# Connector_Sheet.net
KiCad netlist of a schematic drawn in Altium Designer
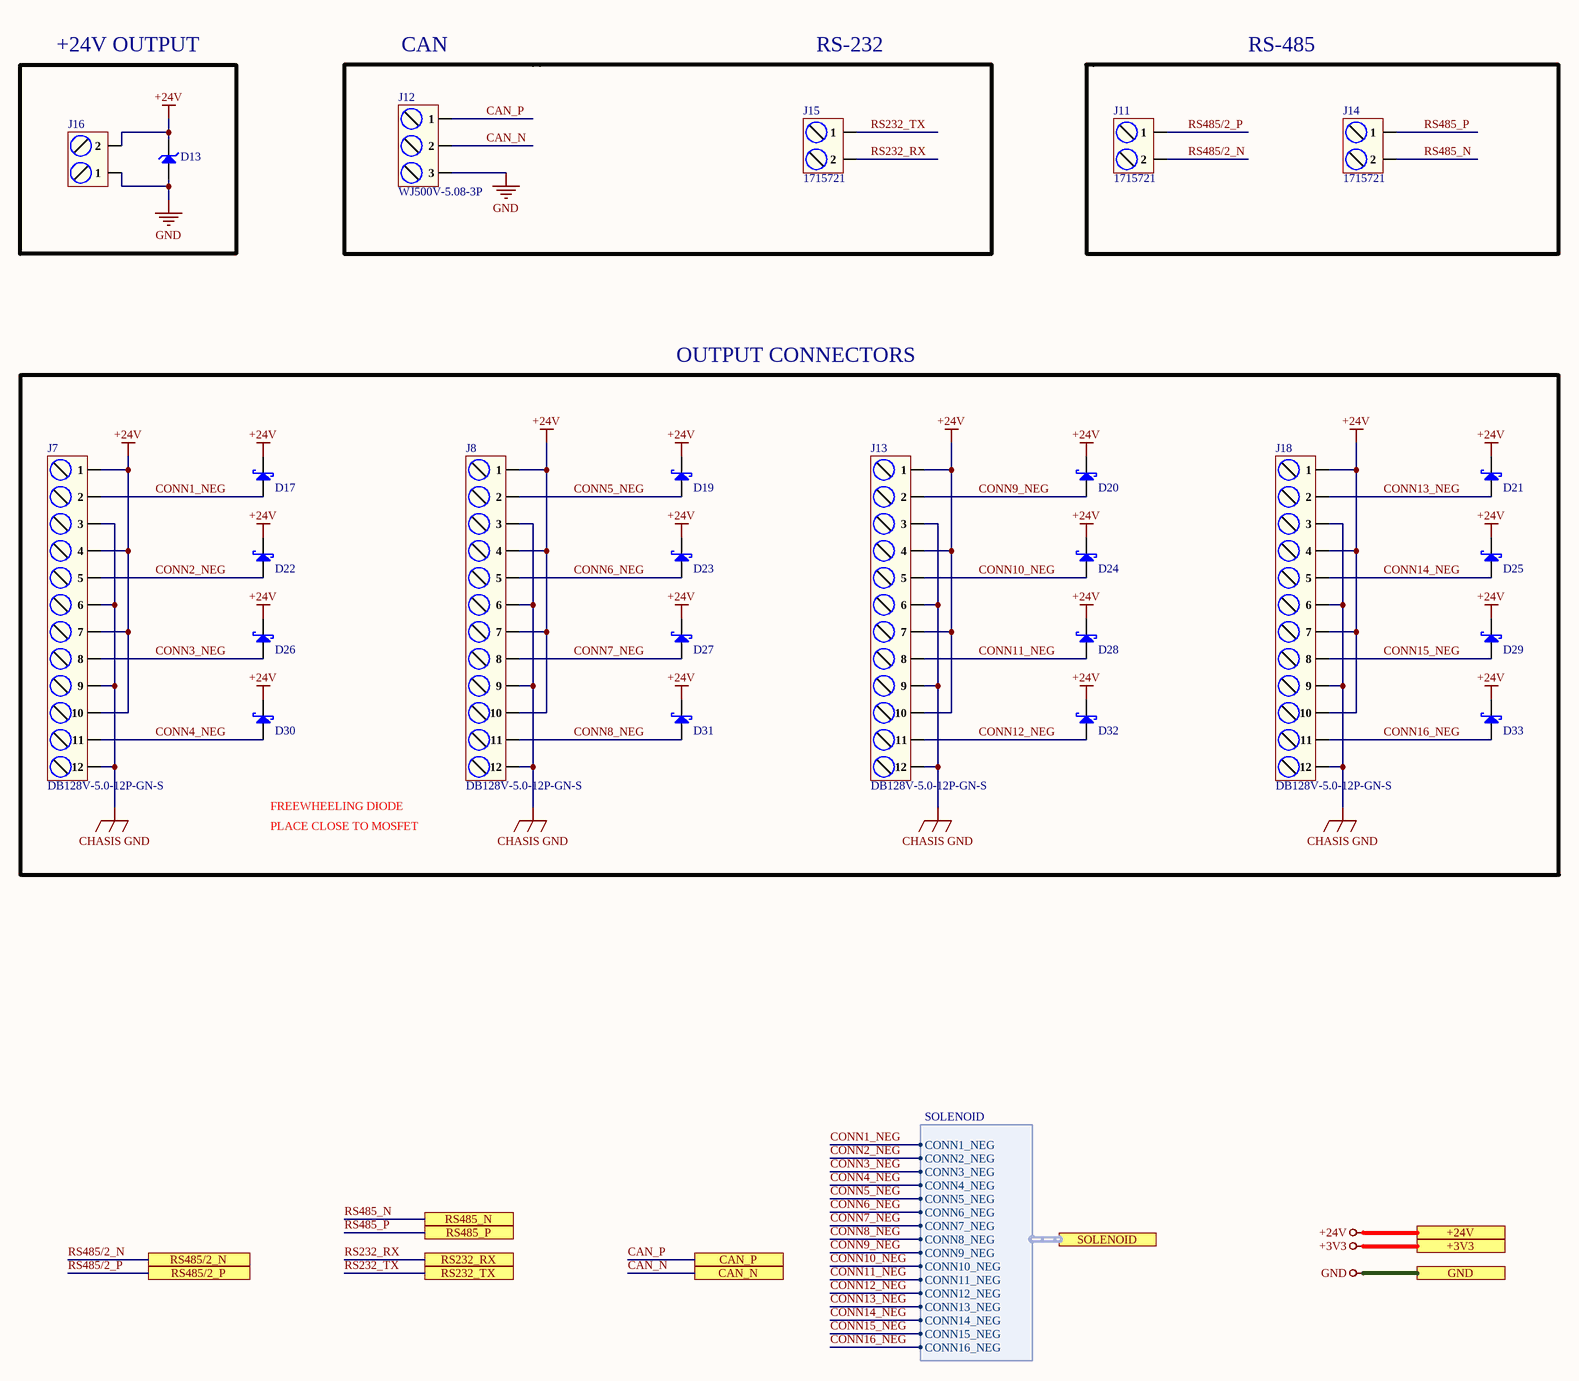
[diagram p0: Connector_Sheet.SchDoc]

(export (version "E")
  (design (tool "Eeschema 10.0.6"))
  (components
    (comp (ref "D13")
      (value "SMBJ28A-13-F")
      (footprint "SMB_")
      (description "TVS DIODE 28VWM 45.4VC SMB")
      (fields (field (name "MANUFACTURER") "Diodes"))
      (libsource (lib "eSpark Libraries") (part "SMBJ28A-13-F"))
    )
    (comp (ref "D17")
      (value "B150-13-F")
      (footprint "SMA")
      (description "DIODE SCHOTTKY 50V 1A SMA")
      (fields (field (name "MANUFACTURER") "Diodes Incorporated") (field (name "LCSC PART NUMBER") "C134431"))
      (libsource (lib "eSpark Libraries") (part "B150-13-F"))
    )
    (comp (ref "D19")
      (value "B150-13-F")
      (footprint "SMA")
      (description "DIODE SCHOTTKY 50V 1A SMA")
      (fields (field (name "MANUFACTURER") "Diodes Incorporated") (field (name "LCSC PART NUMBER") "C134431"))
      (libsource (lib "eSpark Libraries") (part "B150-13-F"))
    )
    (comp (ref "D20")
      (value "B150-13-F")
      (footprint "SMA")
      (description "DIODE SCHOTTKY 50V 1A SMA")
      (fields (field (name "MANUFACTURER") "Diodes Incorporated") (field (name "LCSC PART NUMBER") "C134431"))
      (libsource (lib "eSpark Libraries") (part "B150-13-F"))
    )
    (comp (ref "D21")
      (value "B150-13-F")
      (footprint "SMA")
      (description "DIODE SCHOTTKY 50V 1A SMA")
      (fields (field (name "MANUFACTURER") "Diodes Incorporated") (field (name "LCSC PART NUMBER") "C134431"))
      (libsource (lib "eSpark Libraries") (part "B150-13-F"))
    )
    (comp (ref "D22")
      (value "B150-13-F")
      (footprint "SMA")
      (description "DIODE SCHOTTKY 50V 1A SMA")
      (fields (field (name "MANUFACTURER") "Diodes Incorporated") (field (name "LCSC PART NUMBER") "C134431"))
      (libsource (lib "eSpark Libraries") (part "B150-13-F"))
    )
    (comp (ref "D23")
      (value "B150-13-F")
      (footprint "SMA")
      (description "DIODE SCHOTTKY 50V 1A SMA")
      (fields (field (name "MANUFACTURER") "Diodes Incorporated") (field (name "LCSC PART NUMBER") "C134431"))
      (libsource (lib "eSpark Libraries") (part "B150-13-F"))
    )
    (comp (ref "D24")
      (value "B150-13-F")
      (footprint "SMA")
      (description "DIODE SCHOTTKY 50V 1A SMA")
      (fields (field (name "MANUFACTURER") "Diodes Incorporated") (field (name "LCSC PART NUMBER") "C134431"))
      (libsource (lib "eSpark Libraries") (part "B150-13-F"))
    )
    (comp (ref "D25")
      (value "B150-13-F")
      (footprint "SMA")
      (description "DIODE SCHOTTKY 50V 1A SMA")
      (fields (field (name "MANUFACTURER") "Diodes Incorporated") (field (name "LCSC PART NUMBER") "C134431"))
      (libsource (lib "eSpark Libraries") (part "B150-13-F"))
    )
    (comp (ref "D26")
      (value "B150-13-F")
      (footprint "SMA")
      (description "DIODE SCHOTTKY 50V 1A SMA")
      (fields (field (name "MANUFACTURER") "Diodes Incorporated") (field (name "LCSC PART NUMBER") "C134431"))
      (libsource (lib "eSpark Libraries") (part "B150-13-F"))
    )
    (comp (ref "D27")
      (value "B150-13-F")
      (footprint "SMA")
      (description "DIODE SCHOTTKY 50V 1A SMA")
      (fields (field (name "MANUFACTURER") "Diodes Incorporated") (field (name "LCSC PART NUMBER") "C134431"))
      (libsource (lib "eSpark Libraries") (part "B150-13-F"))
    )
    (comp (ref "D28")
      (value "B150-13-F")
      (footprint "SMA")
      (description "DIODE SCHOTTKY 50V 1A SMA")
      (fields (field (name "MANUFACTURER") "Diodes Incorporated") (field (name "LCSC PART NUMBER") "C134431"))
      (libsource (lib "eSpark Libraries") (part "B150-13-F"))
    )
    (comp (ref "D29")
      (value "B150-13-F")
      (footprint "SMA")
      (description "DIODE SCHOTTKY 50V 1A SMA")
      (fields (field (name "MANUFACTURER") "Diodes Incorporated") (field (name "LCSC PART NUMBER") "C134431"))
      (libsource (lib "eSpark Libraries") (part "B150-13-F"))
    )
    (comp (ref "D30")
      (value "B150-13-F")
      (footprint "SMA")
      (description "DIODE SCHOTTKY 50V 1A SMA")
      (fields (field (name "MANUFACTURER") "Diodes Incorporated") (field (name "LCSC PART NUMBER") "C134431"))
      (libsource (lib "eSpark Libraries") (part "B150-13-F"))
    )
    (comp (ref "D31")
      (value "B150-13-F")
      (footprint "SMA")
      (description "DIODE SCHOTTKY 50V 1A SMA")
      (fields (field (name "MANUFACTURER") "Diodes Incorporated") (field (name "LCSC PART NUMBER") "C134431"))
      (libsource (lib "eSpark Libraries") (part "B150-13-F"))
    )
    (comp (ref "D32")
      (value "B150-13-F")
      (footprint "SMA")
      (description "DIODE SCHOTTKY 50V 1A SMA")
      (fields (field (name "MANUFACTURER") "Diodes Incorporated") (field (name "LCSC PART NUMBER") "C134431"))
      (libsource (lib "eSpark Libraries") (part "B150-13-F"))
    )
    (comp (ref "D33")
      (value "B150-13-F")
      (footprint "SMA")
      (description "DIODE SCHOTTKY 50V 1A SMA")
      (fields (field (name "MANUFACTURER") "Diodes Incorporated") (field (name "LCSC PART NUMBER") "C134431"))
      (libsource (lib "eSpark Libraries") (part "B150-13-F"))
    )
    (comp (ref "J7")
      (value "DB128V-5.0-12P-GN-S")
      (footprint "DB128V-5.0-12P-GN-S")
      (fields (field (name "MANUFACTURER") "DORABO") (field (name "LCSC PART NUMBER") "C424688"))
      (libsource (lib "eSpark Libraries") (part "DB128V-5.0-12P-GN-S"))
    )
    (comp (ref "J8")
      (value "DB128V-5.0-12P-GN-S")
      (footprint "DB128V-5.0-12P-GN-S")
      (fields (field (name "MANUFACTURER") "DORABO") (field (name "LCSC PART NUMBER") "C424688"))
      (libsource (lib "eSpark Libraries") (part "DB128V-5.0-12P-GN-S"))
    )
    (comp (ref "J11")
      (value "1715721")
      (footprint "1715721")
      (description "TERM BLK 2P SIDE ENT 5.08MM PCB")
      (fields (field (name "MANUFACTURER") "Phoenix Contact"))
      (libsource (lib "eSpark Libraries") (part "1715721"))
    )
    (comp (ref "J12")
      (value "WJ500V-5.08-3P")
      (footprint "WJ500V-5.08-3P")
      (fields (field (name "MANUFACTURER") "Ningbo Kangnex Elec") (field (name "LCSC PART NUMBER") "C72334"))
      (libsource (lib "eSpark Libraries") (part "WJ500V-5.08-3P"))
    )
    (comp (ref "J13")
      (value "DB128V-5.0-12P-GN-S")
      (footprint "DB128V-5.0-12P-GN-S")
      (fields (field (name "MANUFACTURER") "DORABO") (field (name "LCSC PART NUMBER") "C424688"))
      (libsource (lib "eSpark Libraries") (part "DB128V-5.0-12P-GN-S"))
    )
    (comp (ref "J14")
      (value "1715721")
      (footprint "1715721")
      (description "TERM BLK 2P SIDE ENT 5.08MM PCB")
      (fields (field (name "MANUFACTURER") "Phoenix Contact"))
      (libsource (lib "eSpark Libraries") (part "1715721"))
    )
    (comp (ref "J15")
      (value "1715721")
      (footprint "1715721")
      (description "TERM BLK 2P SIDE ENT 5.08MM PCB")
      (fields (field (name "MANUFACTURER") "Phoenix Contact"))
      (libsource (lib "eSpark Libraries") (part "1715721"))
    )
    (comp (ref "J16")
      (value "MXHB9500-9.5-02P-BK01-Cu-S-A")
      (footprint "MXHB9500-9.5-02P-BK01-Cu-S-A")
      (fields (field (name "MANUFACTURER") "MAX") (field (name "LCSC PART NUMBER") "C7542168"))
      (libsource (lib "eSpark Libraries") (part "MXHB9500-9.5-02P-BK01-Cu-S-A"))
    )
    (comp (ref "J18")
      (value "DB128V-5.0-12P-GN-S")
      (footprint "DB128V-5.0-12P-GN-S")
      (fields (field (name "MANUFACTURER") "DORABO") (field (name "LCSC PART NUMBER") "C424688"))
      (libsource (lib "eSpark Libraries") (part "DB128V-5.0-12P-GN-S"))
    )
  )
  (nets
    (net (code "3") (name "+24V") (class "Default")
      (node (ref "D13") (pin "2") (pinfunction "K_2") (pintype "passive"))
      (node (ref "D17") (pin "1") (pinfunction "K_1") (pintype "passive"))
      (node (ref "D19") (pin "1") (pinfunction "K_1") (pintype "passive"))
      (node (ref "D20") (pin "1") (pinfunction "K_1") (pintype "passive"))
      (node (ref "D21") (pin "1") (pinfunction "K_1") (pintype "passive"))
      (node (ref "D22") (pin "1") (pinfunction "K_1") (pintype "passive"))
      (node (ref "D23") (pin "1") (pinfunction "K_1") (pintype "passive"))
      (node (ref "D24") (pin "1") (pinfunction "K_1") (pintype "passive"))
      (node (ref "D25") (pin "1") (pinfunction "K_1") (pintype "passive"))
      (node (ref "D26") (pin "1") (pinfunction "K_1") (pintype "passive"))
      (node (ref "D27") (pin "1") (pinfunction "K_1") (pintype "passive"))
      (node (ref "D28") (pin "1") (pinfunction "K_1") (pintype "passive"))
      (node (ref "D29") (pin "1") (pinfunction "K_1") (pintype "passive"))
      (node (ref "D30") (pin "1") (pinfunction "K_1") (pintype "passive"))
      (node (ref "D31") (pin "1") (pinfunction "K_1") (pintype "passive"))
      (node (ref "D32") (pin "1") (pinfunction "K_1") (pintype "passive"))
      (node (ref "D33") (pin "1") (pinfunction "K_1") (pintype "passive"))
      (node (ref "J13") (pin "1") (pinfunction "1_1") (pintype "passive"))
      (node (ref "J13") (pin "10") (pinfunction "10_10") (pintype "passive"))
      (node (ref "J13") (pin "4") (pinfunction "4_4") (pintype "passive"))
      (node (ref "J13") (pin "7") (pinfunction "7_7") (pintype "passive"))
      (node (ref "J16") (pin "2") (pinfunction "2_2") (pintype "passive"))
      (node (ref "J18") (pin "1") (pinfunction "1_1") (pintype "passive"))
      (node (ref "J18") (pin "10") (pinfunction "10_10") (pintype "passive"))
      (node (ref "J18") (pin "4") (pinfunction "4_4") (pintype "passive"))
      (node (ref "J18") (pin "7") (pinfunction "7_7") (pintype "passive"))
      (node (ref "J7") (pin "1") (pinfunction "1_1") (pintype "passive"))
      (node (ref "J7") (pin "10") (pinfunction "10_10") (pintype "passive"))
      (node (ref "J7") (pin "4") (pinfunction "4_4") (pintype "passive"))
      (node (ref "J7") (pin "7") (pinfunction "7_7") (pintype "passive"))
      (node (ref "J8") (pin "1") (pinfunction "1_1") (pintype "passive"))
      (node (ref "J8") (pin "10") (pinfunction "10_10") (pintype "passive"))
      (node (ref "J8") (pin "4") (pinfunction "4_4") (pintype "passive"))
      (node (ref "J8") (pin "7") (pinfunction "7_7") (pintype "passive"))
    )
    (net (code "4") (name "/CAN_N") (class "Default")
      (node (ref "J12") (pin "2") (pinfunction "2_2") (pintype "passive"))
    )
    (net (code "5") (name "/CAN_P") (class "Default")
      (node (ref "J12") (pin "1") (pinfunction "1_1") (pintype "passive"))
    )
    (net (code "6") (name "/CONN1_NEG") (class "Default")
      (node (ref "D17") (pin "2") (pinfunction "A_2") (pintype "passive"))
      (node (ref "J7") (pin "2") (pinfunction "2_2") (pintype "passive"))
    )
    (net (code "7") (name "/CONN2_NEG") (class "Default")
      (node (ref "D22") (pin "2") (pinfunction "A_2") (pintype "passive"))
      (node (ref "J7") (pin "5") (pinfunction "5_5") (pintype "passive"))
    )
    (net (code "8") (name "/CONN3_NEG") (class "Default")
      (node (ref "D26") (pin "2") (pinfunction "A_2") (pintype "passive"))
      (node (ref "J7") (pin "8") (pinfunction "8_8") (pintype "passive"))
    )
    (net (code "9") (name "/CONN4_NEG") (class "Default")
      (node (ref "D30") (pin "2") (pinfunction "A_2") (pintype "passive"))
      (node (ref "J7") (pin "11") (pinfunction "11_11") (pintype "passive"))
    )
    (net (code "10") (name "/CONN5_NEG") (class "Default")
      (node (ref "D19") (pin "2") (pinfunction "A_2") (pintype "passive"))
      (node (ref "J8") (pin "2") (pinfunction "2_2") (pintype "passive"))
    )
    (net (code "11") (name "/CONN6_NEG") (class "Default")
      (node (ref "D23") (pin "2") (pinfunction "A_2") (pintype "passive"))
      (node (ref "J8") (pin "5") (pinfunction "5_5") (pintype "passive"))
    )
    (net (code "12") (name "/CONN7_NEG") (class "Default")
      (node (ref "D27") (pin "2") (pinfunction "A_2") (pintype "passive"))
      (node (ref "J8") (pin "8") (pinfunction "8_8") (pintype "passive"))
    )
    (net (code "13") (name "/CONN8_NEG") (class "Default")
      (node (ref "D31") (pin "2") (pinfunction "A_2") (pintype "passive"))
      (node (ref "J8") (pin "11") (pinfunction "11_11") (pintype "passive"))
    )
    (net (code "14") (name "/CONN9_NEG") (class "Default")
      (node (ref "D20") (pin "2") (pinfunction "A_2") (pintype "passive"))
      (node (ref "J13") (pin "2") (pinfunction "2_2") (pintype "passive"))
    )
    (net (code "15") (name "/CONN10_NEG") (class "Default")
      (node (ref "D24") (pin "2") (pinfunction "A_2") (pintype "passive"))
      (node (ref "J13") (pin "5") (pinfunction "5_5") (pintype "passive"))
    )
    (net (code "16") (name "/CONN11_NEG") (class "Default")
      (node (ref "D28") (pin "2") (pinfunction "A_2") (pintype "passive"))
      (node (ref "J13") (pin "8") (pinfunction "8_8") (pintype "passive"))
    )
    (net (code "17") (name "/CONN12_NEG") (class "Default")
      (node (ref "D32") (pin "2") (pinfunction "A_2") (pintype "passive"))
      (node (ref "J13") (pin "11") (pinfunction "11_11") (pintype "passive"))
    )
    (net (code "18") (name "/CONN13_NEG") (class "Default")
      (node (ref "D21") (pin "2") (pinfunction "A_2") (pintype "passive"))
      (node (ref "J18") (pin "2") (pinfunction "2_2") (pintype "passive"))
    )
    (net (code "19") (name "/CONN14_NEG") (class "Default")
      (node (ref "D25") (pin "2") (pinfunction "A_2") (pintype "passive"))
      (node (ref "J18") (pin "5") (pinfunction "5_5") (pintype "passive"))
    )
    (net (code "20") (name "/CONN15_NEG") (class "Default")
      (node (ref "D29") (pin "2") (pinfunction "A_2") (pintype "passive"))
      (node (ref "J18") (pin "8") (pinfunction "8_8") (pintype "passive"))
    )
    (net (code "21") (name "/CONN16_NEG") (class "Default")
      (node (ref "D33") (pin "2") (pinfunction "A_2") (pintype "passive"))
      (node (ref "J18") (pin "11") (pinfunction "11_11") (pintype "passive"))
    )
    (net (code "22") (name "/RS232_RX") (class "Default")
      (node (ref "J15") (pin "2") (pinfunction "2_2") (pintype "passive"))
    )
    (net (code "23") (name "/RS232_TX") (class "Default")
      (node (ref "J15") (pin "1") (pinfunction "1_1") (pintype "passive"))
    )
    (net (code "24") (name "/RS485_N") (class "Default")
      (node (ref "J14") (pin "2") (pinfunction "2_2") (pintype "passive"))
    )
    (net (code "25") (name "/RS485_P") (class "Default")
      (node (ref "J14") (pin "1") (pinfunction "1_1") (pintype "passive"))
    )
    (net (code "26") (name "/RS485{slash}2_N") (class "Default")
      (node (ref "J11") (pin "2") (pinfunction "2_2") (pintype "passive"))
    )
    (net (code "27") (name "/RS485{slash}2_P") (class "Default")
      (node (ref "J11") (pin "1") (pinfunction "1_1") (pintype "passive"))
    )
    (net (code "29") (name "CHASIS GND") (class "Default")
      (node (ref "J13") (pin "12") (pinfunction "12_12") (pintype "passive"))
      (node (ref "J13") (pin "3") (pinfunction "3_3") (pintype "passive"))
      (node (ref "J13") (pin "6") (pinfunction "6_6") (pintype "passive"))
      (node (ref "J13") (pin "9") (pinfunction "9_9") (pintype "passive"))
      (node (ref "J18") (pin "12") (pinfunction "12_12") (pintype "passive"))
      (node (ref "J18") (pin "3") (pinfunction "3_3") (pintype "passive"))
      (node (ref "J18") (pin "6") (pinfunction "6_6") (pintype "passive"))
      (node (ref "J18") (pin "9") (pinfunction "9_9") (pintype "passive"))
      (node (ref "J7") (pin "12") (pinfunction "12_12") (pintype "passive"))
      (node (ref "J7") (pin "3") (pinfunction "3_3") (pintype "passive"))
      (node (ref "J7") (pin "6") (pinfunction "6_6") (pintype "passive"))
      (node (ref "J7") (pin "9") (pinfunction "9_9") (pintype "passive"))
      (node (ref "J8") (pin "12") (pinfunction "12_12") (pintype "passive"))
      (node (ref "J8") (pin "3") (pinfunction "3_3") (pintype "passive"))
      (node (ref "J8") (pin "6") (pinfunction "6_6") (pintype "passive"))
      (node (ref "J8") (pin "9") (pinfunction "9_9") (pintype "passive"))
    )
    (net (code "30") (name "GND") (class "Default")
      (node (ref "D13") (pin "1") (pinfunction "A_1") (pintype "passive"))
      (node (ref "J12") (pin "3") (pinfunction "3_3") (pintype "passive"))
      (node (ref "J16") (pin "1") (pinfunction "1_1") (pintype "passive"))
    )
  )
)
